# MJ808_clone_-_all_driver_-_23mm.net
KiCad netlist of a schematic drawn in EAGLE
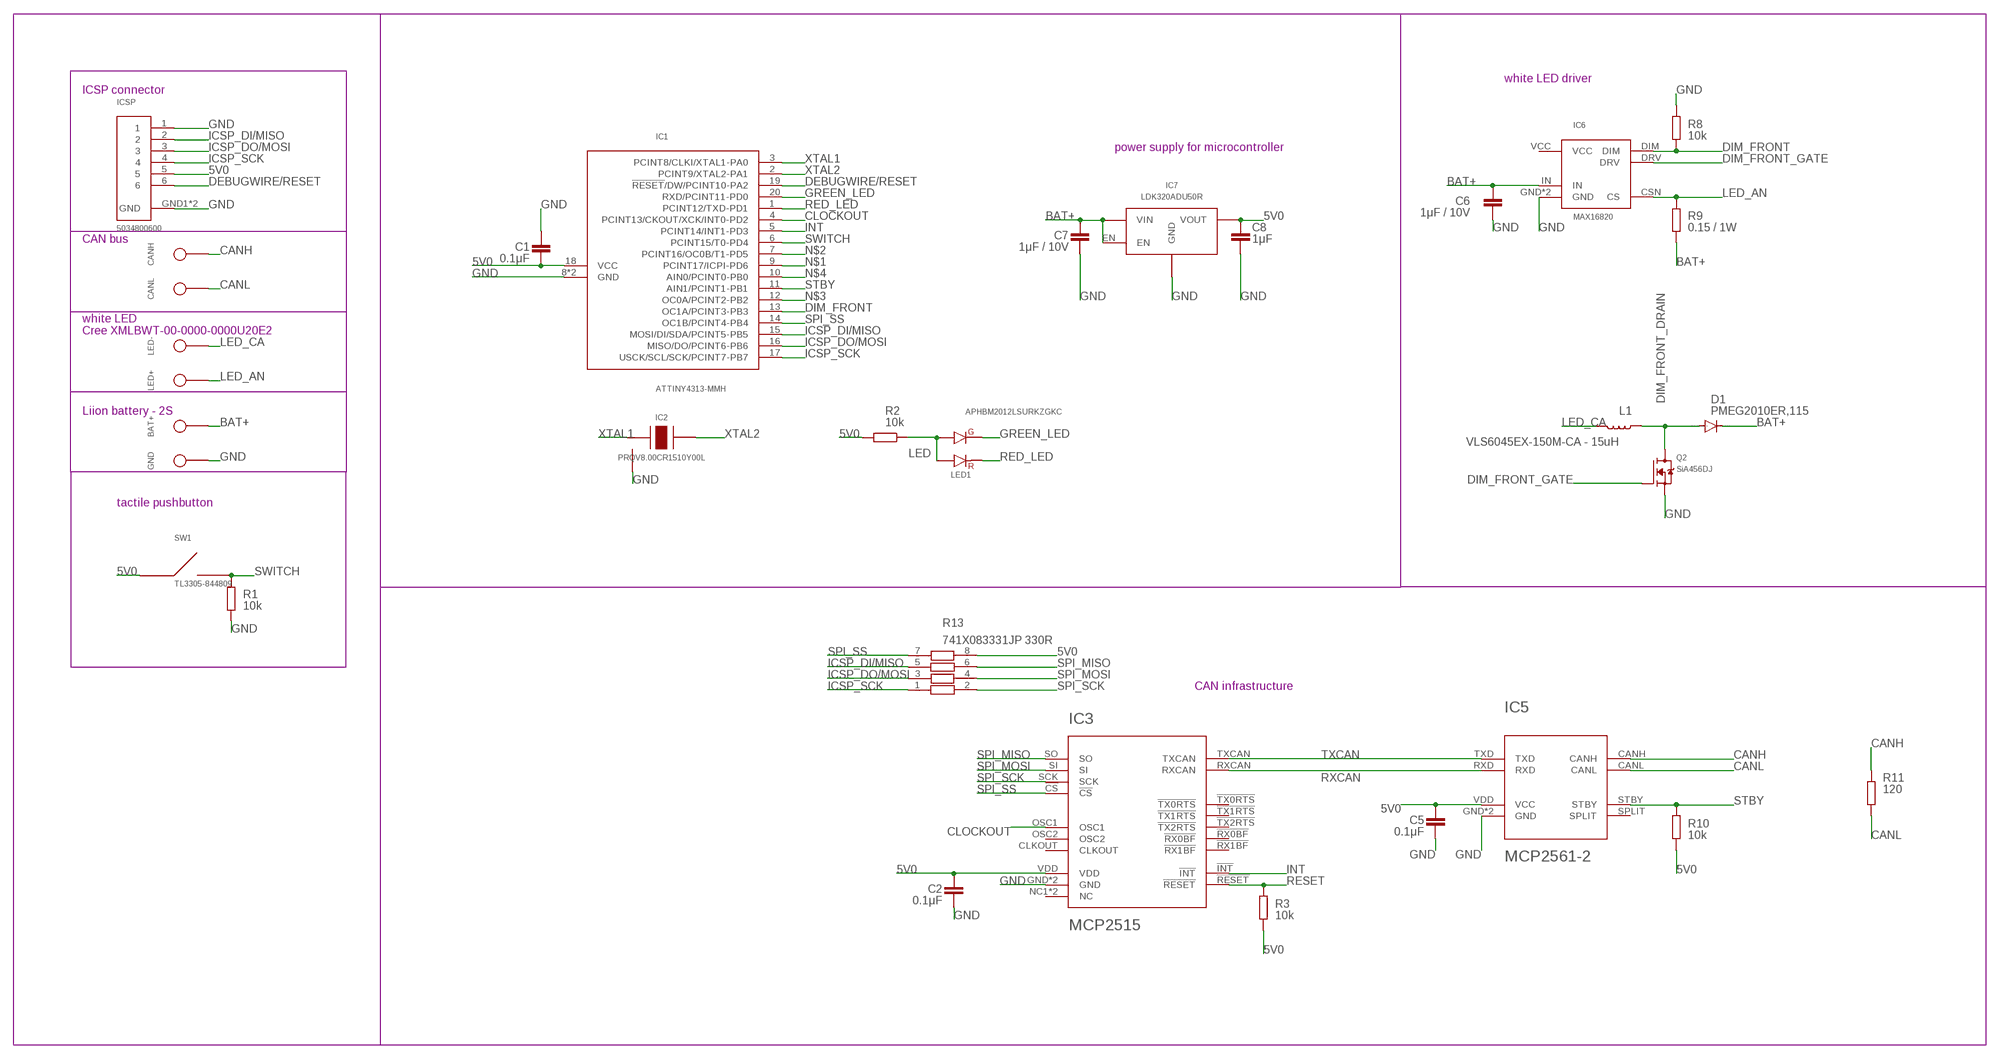
[diagram p0: schematic, sheet 1]

(export (version "E")
  (design (tool "Eeschema 10.0.6"))
  (components
    (comp (ref "BAT+")
      (value "LiIon + Terminal")
      (footprint "eagle-import:TH")
      (libsource (lib "eagle-import") (part "TP"))
    )
    (comp (ref "C1")
      (value "0.1μF")
      (footprint "eagle-import:C0402")
      (libsource (lib "eagle-import") (part "C-EUC0402"))
    )
    (comp (ref "C2")
      (value "0.1μF")
      (footprint "eagle-import:C0402")
      (libsource (lib "eagle-import") (part "C-EUC0402"))
    )
    (comp (ref "C5")
      (value "0.1μF")
      (footprint "eagle-import:C0402")
      (libsource (lib "eagle-import") (part "C-EUC0402"))
    )
    (comp (ref "C6")
      (value "1μF / 10V")
      (footprint "eagle-import:C0402")
      (libsource (lib "eagle-import") (part "C-EUC0402"))
    )
    (comp (ref "C7")
      (value "1μF / 10V")
      (footprint "eagle-import:C0402")
      (libsource (lib "eagle-import") (part "C-EUC0402"))
    )
    (comp (ref "C8")
      (value "1μF")
      (footprint "eagle-import:C0402")
      (libsource (lib "eagle-import") (part "C-EUC0402"))
    )
    (comp (ref "CANH")
      (value "CAN high")
      (footprint "eagle-import:TH")
      (libsource (lib "eagle-import") (part "TP"))
    )
    (comp (ref "CANL")
      (value "CAN low")
      (footprint "eagle-import:TH")
      (libsource (lib "eagle-import") (part "TP"))
    )
    (comp (ref "D1")
      (value "PMEG2010ER,115")
      (footprint "eagle-import:SOD123")
      (libsource (lib "eagle-import") (part "DIODE-SOD123"))
    )
    (comp (ref "GND")
      (value "LiIon - Terminal")
      (footprint "eagle-import:TH")
      (libsource (lib "eagle-import") (part "TP"))
    )
    (comp (ref "IC1")
      (value "ATTINY4313-MMH")
      (footprint "eagle-import:VQFN-20")
      (fields (field (name "SPICEPREFIX") "X"))
      (libsource (lib "eagle-import") (part "ATTINY4313VQFN-20"))
    )
    (comp (ref "IC2")
      (value "PRQV8.00CR1510Y00L")
      (footprint "eagle-import:SMT")
      (libsource (lib "eagle-import") (part "PRQV"))
    )
    (comp (ref "IC3")
      (value "MCP2515")
      (footprint "eagle-import:QFN20")
      (libsource (lib "eagle-import") (part "MCP2515-I-ML"))
    )
    (comp (ref "IC5")
      (value "MCP2561-2")
      (footprint "eagle-import:DFN10")
      (libsource (lib "eagle-import") (part "MCP2561-2"))
    )
    (comp (ref "IC6")
      (value "MAX16820")
      (footprint "eagle-import:TDFN-6-EP")
      (libsource (lib "eagle-import") (part "MAX16820"))
    )
    (comp (ref "IC7")
      (value "LDK320ADU50R")
      (footprint "eagle-import:SOT-23-5L")
      (libsource (lib "eagle-import") (part "LDK320SOT-23-5L"))
    )
    (comp (ref "ICSP")
      (value "5034800600")
      (footprint "eagle-import:SMT")
      (libsource (lib "eagle-import") (part "5034800600"))
    )
    (comp (ref "L1")
      (value "VLS6045EX-150M-CA - 15uH")
      (footprint "eagle-import:SRN6045")
      (libsource (lib "eagle-import") (part "INDUCTOR-SRN6045-33UH"))
    )
    (comp (ref "LED+")
      (value "LED anode")
      (footprint "eagle-import:TH")
      (libsource (lib "eagle-import") (part "TP"))
    )
    (comp (ref "LED-")
      (value "LED cathode")
      (footprint "eagle-import:TH")
      (libsource (lib "eagle-import") (part "TP"))
    )
    (comp (ref "LED1")
      (value "APHBM2012LSURKZGKC")
      (footprint "eagle-import:SMD")
      (libsource (lib "eagle-import") (part "APHBM2012LSURKZGKC"))
    )
    (comp (ref "Q2")
      (value "SiA456DJ")
      (footprint "eagle-import:SC-70-6")
      (libsource (lib "eagle-import") (part "SIA456DJ"))
    )
    (comp (ref "R1")
      (value "10k")
      (footprint "eagle-import:R0402")
      (libsource (lib "eagle-import") (part "R-EU_R0402"))
    )
    (comp (ref "R2")
      (value "10k")
      (footprint "eagle-import:R0402")
      (libsource (lib "eagle-import") (part "R-EU_R0402"))
    )
    (comp (ref "R3")
      (value "10k")
      (footprint "eagle-import:R0402")
      (libsource (lib "eagle-import") (part "R-EU_R0402"))
    )
    (comp (ref "R8")
      (value "10k")
      (footprint "eagle-import:R0402")
      (libsource (lib "eagle-import") (part "R-EU_R0402"))
    )
    (comp (ref "R9")
      (value "0.15 / 1W")
      (footprint "eagle-import:R1210")
      (libsource (lib "eagle-import") (part "R-EU_R1210"))
    )
    (comp (ref "R10")
      (value "10k")
      (footprint "eagle-import:R0402")
      (libsource (lib "eagle-import") (part "R-EU_R0402"))
    )
    (comp (ref "R11")
      (value "120")
      (footprint "eagle-import:R0805")
      (libsource (lib "eagle-import") (part "R-EU_R0805"))
    )
    (comp (ref "R13")
      (value "741X083331JP 330R")
      (footprint "eagle-import:0402")
      (libsource (lib "eagle-import") (part "741X083331JP"))
    )
    (comp (ref "SW1")
      (value "TL3305-844809")
      (footprint "eagle-import:SMD")
      (libsource (lib "eagle-import") (part "TL3305-844809"))
    )
  )
  (nets
    (net (code "1") (name "/5V0") (class "Default")
      (node (ref "C1") (pin "1") (pinfunction "1_1") (pintype "passive"))
      (node (ref "C2") (pin "1") (pinfunction "1_1") (pintype "passive"))
      (node (ref "C5") (pin "1") (pinfunction "1_1") (pintype "passive"))
      (node (ref "C8") (pin "2") (pinfunction "2_2") (pintype "passive"))
      (node (ref "IC1") (pin "18") (pinfunction "VCC_18") (pintype "bidirectional"))
      (node (ref "IC3") (pin "VDD") (pinfunction "VDD_VDD") (pintype "power_in"))
      (node (ref "IC5") (pin "VDD") (pinfunction "VCC_VDD") (pintype "power_in"))
      (node (ref "IC7") (pin "OUT") (pinfunction "VOUT_OUT") (pintype "bidirectional"))
      (node (ref "ICSP") (pin "5") (pinfunction "5_5") (pintype "bidirectional"))
      (node (ref "R10") (pin "1") (pinfunction "1_1") (pintype "passive"))
      (node (ref "R13") (pin "8") (pinfunction "8_8") (pintype "bidirectional"))
      (node (ref "R2") (pin "2") (pinfunction "2_2") (pintype "passive"))
      (node (ref "R3") (pin "1") (pinfunction "1_1") (pintype "passive"))
      (node (ref "SW1") (pin "1") (pinfunction "P$1_1") (pintype "bidirectional"))
      (node (ref "SW1") (pin "2") (pinfunction "P$1_2") (pintype "bidirectional"))
    )
    (net (code "2") (name "/BAT+") (class "Default")
      (node (ref "BAT+") (pin "TP$1") (pinfunction "TP$1_TP$1") (pintype "bidirectional"))
      (node (ref "C6") (pin "1") (pinfunction "1_1") (pintype "passive"))
      (node (ref "C7") (pin "1") (pinfunction "1_1") (pintype "passive"))
      (node (ref "D1") (pin "C") (pinfunction "C_C") (pintype "passive"))
      (node (ref "IC6") (pin "IN") (pinfunction "IN_IN") (pintype "power_in"))
      (node (ref "IC7") (pin "EN") (pinfunction "EN_EN") (pintype "bidirectional"))
      (node (ref "IC7") (pin "IN") (pinfunction "VIN_IN") (pintype "bidirectional"))
      (node (ref "R9") (pin "2") (pinfunction "2_2") (pintype "passive"))
    )
    (net (code "3") (name "/CANH") (class "Default")
      (node (ref "CANH") (pin "TP$1") (pinfunction "TP$1_TP$1") (pintype "bidirectional"))
      (node (ref "IC5") (pin "CANH") (pinfunction "CANH_CANH") (pintype "bidirectional"))
      (node (ref "R11") (pin "2") (pinfunction "2_2") (pintype "passive"))
    )
    (net (code "4") (name "/CANL") (class "Default")
      (node (ref "CANL") (pin "TP$1") (pinfunction "TP$1_TP$1") (pintype "bidirectional"))
      (node (ref "IC5") (pin "CANL") (pinfunction "CANL_CANL") (pintype "bidirectional"))
      (node (ref "R11") (pin "1") (pinfunction "1_1") (pintype "passive"))
    )
    (net (code "5") (name "/CLOCKOUT") (class "Default")
      (node (ref "IC1") (pin "4") (pinfunction "PCINT13/CKOUT/XCK/INT0-PD2_4") (pintype "bidirectional"))
      (node (ref "IC3") (pin "OSC1") (pinfunction "OSC1_OSC1") (pintype "bidirectional"))
    )
    (net (code "6") (name "/DEBUGWIRE{slash}RESET") (class "Default")
      (node (ref "IC1") (pin "19") (pinfunction "~{RESET}/DW/PCINT10-PA2_19") (pintype "bidirectional"))
      (node (ref "ICSP") (pin "6") (pinfunction "6_6") (pintype "bidirectional"))
    )
    (net (code "7") (name "/DIM_FRONT") (class "Default")
      (node (ref "IC1") (pin "13") (pinfunction "OC1A/PCINT3-PB3_13") (pintype "bidirectional"))
      (node (ref "IC6") (pin "DIM") (pinfunction "DIM_DIM") (pintype "bidirectional"))
      (node (ref "R8") (pin "1") (pinfunction "1_1") (pintype "passive"))
    )
    (net (code "8") (name "/DIM_FRONT_DRAIN") (class "Default")
      (node (ref "D1") (pin "A") (pinfunction "A_A") (pintype "passive"))
      (node (ref "L1") (pin "1") (pinfunction "1_1") (pintype "passive"))
      (node (ref "Q2") (pin "1D") (pinfunction "D_1D") (pintype "passive"))
      (node (ref "Q2") (pin "2D") (pinfunction "D_2D") (pintype "passive"))
      (node (ref "Q2") (pin "5D") (pinfunction "D_5D") (pintype "passive"))
      (node (ref "Q2") (pin "6D") (pinfunction "D_6D") (pintype "passive"))
      (node (ref "Q2") (pin "D") (pinfunction "D_D") (pintype "passive"))
    )
    (net (code "9") (name "/DIM_FRONT_GATE") (class "Default")
      (node (ref "IC6") (pin "DRV") (pinfunction "DRV_DRV") (pintype "bidirectional"))
      (node (ref "Q2") (pin "3G") (pinfunction "G_3G") (pintype "passive"))
    )
    (net (code "10") (name "/GND") (class "Default")
      (node (ref "C1") (pin "2") (pinfunction "2_2") (pintype "passive"))
      (node (ref "C2") (pin "2") (pinfunction "2_2") (pintype "passive"))
      (node (ref "C5") (pin "2") (pinfunction "2_2") (pintype "passive"))
      (node (ref "C6") (pin "2") (pinfunction "2_2") (pintype "passive"))
      (node (ref "C7") (pin "2") (pinfunction "2_2") (pintype "passive"))
      (node (ref "C8") (pin "1") (pinfunction "1_1") (pintype "passive"))
      (node (ref "GND") (pin "TP$1") (pinfunction "TP$1_TP$1") (pintype "bidirectional"))
      (node (ref "IC1") (pin "8") (pinfunction "GND_8") (pintype "bidirectional"))
      (node (ref "IC1") (pin "GND") (pinfunction "GND_GND") (pintype "bidirectional"))
      (node (ref "IC2") (pin "GND") (pinfunction "GND_GND") (pintype "bidirectional"))
      (node (ref "IC3") (pin "GND") (pinfunction "GND_GND") (pintype "power_in"))
      (node (ref "IC3") (pin "GND6") (pinfunction "GND_GND6") (pintype "power_in"))
      (node (ref "IC5") (pin "GND") (pinfunction "GND_GND") (pintype "power_in"))
      (node (ref "IC5") (pin "VSS") (pinfunction "GND_VSS") (pintype "power_in"))
      (node (ref "IC6") (pin "GND") (pinfunction "GND_GND") (pintype "power_in"))
      (node (ref "IC6") (pin "GND1") (pinfunction "GND_GND1") (pintype "power_in"))
      (node (ref "IC7") (pin "GND") (pinfunction "GND_GND") (pintype "bidirectional"))
      (node (ref "ICSP") (pin "1") (pinfunction "1_1") (pintype "bidirectional"))
      (node (ref "ICSP") (pin "GND1") (pinfunction "GND_GND1") (pintype "bidirectional"))
      (node (ref "ICSP") (pin "GND2") (pinfunction "GND_GND2") (pintype "bidirectional"))
      (node (ref "Q2") (pin "4S") (pinfunction "S_4S") (pintype "passive"))
      (node (ref "Q2") (pin "S") (pinfunction "S_S") (pintype "passive"))
      (node (ref "R1") (pin "2") (pinfunction "2_2") (pintype "passive"))
      (node (ref "R8") (pin "2") (pinfunction "2_2") (pintype "passive"))
    )
    (net (code "11") (name "/GREEN_LED") (class "Default")
      (node (ref "IC1") (pin "20") (pinfunction "RXD/PCINT11-PD0_20") (pintype "bidirectional"))
      (node (ref "LED1") (pin "3") (pinfunction "3_3") (pintype "bidirectional"))
    )
    (net (code "12") (name "/ICSP_DI{slash}MISO") (class "Default")
      (node (ref "IC1") (pin "15") (pinfunction "MOSI/DI/SDA/PCINT5-PB5_15") (pintype "bidirectional"))
      (node (ref "ICSP") (pin "2") (pinfunction "2_2") (pintype "bidirectional"))
      (node (ref "R13") (pin "5") (pinfunction "5_5") (pintype "bidirectional"))
    )
    (net (code "13") (name "/ICSP_DO{slash}MOSI") (class "Default")
      (node (ref "IC1") (pin "16") (pinfunction "MISO/DO/PCINT6-PB6_16") (pintype "bidirectional"))
      (node (ref "ICSP") (pin "3") (pinfunction "3_3") (pintype "bidirectional"))
      (node (ref "R13") (pin "3") (pinfunction "3_3") (pintype "bidirectional"))
    )
    (net (code "14") (name "/ICSP_SCK") (class "Default")
      (node (ref "IC1") (pin "17") (pinfunction "USCK/SCL/SCK/PCINT7-PB7_17") (pintype "bidirectional"))
      (node (ref "ICSP") (pin "4") (pinfunction "4_4") (pintype "bidirectional"))
      (node (ref "R13") (pin "1") (pinfunction "1_1") (pintype "bidirectional"))
    )
    (net (code "15") (name "/INT") (class "Default")
      (node (ref "IC1") (pin "5") (pinfunction "PCINT14/INT1-PD3_5") (pintype "bidirectional"))
      (node (ref "IC3") (pin "!INT!") (pinfunction "~{INT}_!INT!") (pintype "bidirectional"))
    )
    (net (code "16") (name "/LED") (class "Default")
      (node (ref "LED1") (pin "1") (pinfunction "1_1") (pintype "bidirectional"))
      (node (ref "LED1") (pin "4") (pinfunction "4_4") (pintype "bidirectional"))
      (node (ref "R2") (pin "1") (pinfunction "1_1") (pintype "passive"))
    )
    (net (code "17") (name "/LED_AN") (class "Default")
      (node (ref "IC6") (pin "CSN") (pinfunction "CS_CSN") (pintype "bidirectional"))
      (node (ref "LED+") (pin "TP$1") (pinfunction "TP$1_TP$1") (pintype "bidirectional"))
      (node (ref "R9") (pin "1") (pinfunction "1_1") (pintype "passive"))
    )
    (net (code "18") (name "/LED_CA") (class "Default")
      (node (ref "L1") (pin "2") (pinfunction "2_2") (pintype "passive"))
      (node (ref "LED-") (pin "TP$1") (pinfunction "TP$1_TP$1") (pintype "bidirectional"))
    )
    (net (code "19") (name "/N$1") (class "Default")
      (node (ref "IC1") (pin "9") (pinfunction "PCINT17/ICPI-PD6_9") (pintype "bidirectional"))
    )
    (net (code "20") (name "/N$2") (class "Default")
      (node (ref "IC1") (pin "7") (pinfunction "PCINT16/OC0B/T1-PD5_7") (pintype "bidirectional"))
    )
    (net (code "21") (name "/N$3") (class "Default")
      (node (ref "IC1") (pin "12") (pinfunction "OC0A/PCINT2-PB2_12") (pintype "bidirectional"))
    )
    (net (code "22") (name "/N$4") (class "Default")
      (node (ref "IC1") (pin "10") (pinfunction "AIN0/PCINT0-PB0_10") (pintype "bidirectional"))
    )
    (net (code "23") (name "/RED_LED") (class "Default")
      (node (ref "IC1") (pin "1") (pinfunction "PCINT12/TXD-PD1_1") (pintype "bidirectional"))
      (node (ref "LED1") (pin "2") (pinfunction "2_2") (pintype "bidirectional"))
    )
    (net (code "24") (name "/RESET") (class "Default")
      (node (ref "IC3") (pin "!RESET!") (pinfunction "~{RESET}_!RESET!") (pintype "bidirectional"))
      (node (ref "R3") (pin "2") (pinfunction "2_2") (pintype "passive"))
    )
    (net (code "25") (name "/RXCAN") (class "Default")
      (node (ref "IC3") (pin "RXCAN") (pinfunction "RXCAN_RXCAN") (pintype "input"))
      (node (ref "IC5") (pin "RXD") (pinfunction "RXD_RXD") (pintype "output"))
    )
    (net (code "26") (name "/SPI_MISO") (class "Default")
      (node (ref "IC3") (pin "SO") (pinfunction "SO_SO") (pintype "output"))
      (node (ref "R13") (pin "6") (pinfunction "6_6") (pintype "bidirectional"))
    )
    (net (code "27") (name "/SPI_MOSI") (class "Default")
      (node (ref "IC3") (pin "SI") (pinfunction "SI_SI") (pintype "input"))
      (node (ref "R13") (pin "4") (pinfunction "4_4") (pintype "bidirectional"))
    )
    (net (code "28") (name "/SPI_SCK") (class "Default")
      (node (ref "IC3") (pin "SCK") (pinfunction "SCK_SCK") (pintype "bidirectional"))
      (node (ref "R13") (pin "2") (pinfunction "2_2") (pintype "bidirectional"))
    )
    (net (code "29") (name "/SPI_SS") (class "Default")
      (node (ref "IC1") (pin "14") (pinfunction "OC1B/PCINT4-PB4_14") (pintype "bidirectional"))
      (node (ref "IC3") (pin "!CS!") (pinfunction "~{CS}_!CS!") (pintype "bidirectional"))
      (node (ref "R13") (pin "7") (pinfunction "7_7") (pintype "bidirectional"))
    )
    (net (code "30") (name "/STBY") (class "Default")
      (node (ref "IC1") (pin "11") (pinfunction "AIN1/PCINT1-PB1_11") (pintype "bidirectional"))
      (node (ref "IC5") (pin "STBY") (pinfunction "STBY_STBY") (pintype "bidirectional"))
      (node (ref "R10") (pin "2") (pinfunction "2_2") (pintype "passive"))
    )
    (net (code "31") (name "/SWITCH") (class "Default")
      (node (ref "IC1") (pin "6") (pinfunction "PCINT15/T0-PD4_6") (pintype "bidirectional"))
      (node (ref "R1") (pin "1") (pinfunction "1_1") (pintype "passive"))
      (node (ref "SW1") (pin "3") (pinfunction "P$2_3") (pintype "bidirectional"))
      (node (ref "SW1") (pin "4") (pinfunction "P$2_4") (pintype "bidirectional"))
    )
    (net (code "32") (name "/TXCAN") (class "Default")
      (node (ref "IC3") (pin "TXCAN") (pinfunction "TXCAN_TXCAN") (pintype "output"))
      (node (ref "IC5") (pin "TXD") (pinfunction "TXD_TXD") (pintype "input"))
    )
    (net (code "33") (name "/VCC") (class "Default")
      (node (ref "IC6") (pin "VCC") (pinfunction "VCC_VCC") (pintype "power_in"))
    )
    (net (code "34") (name "/XTAL1") (class "Default")
      (node (ref "IC1") (pin "3") (pinfunction "PCINT8/CLKI/XTAL1-PA0_3") (pintype "bidirectional"))
      (node (ref "IC2") (pin "XTAL1") (pinfunction "XTAL1_XTAL1") (pintype "bidirectional"))
    )
    (net (code "35") (name "/XTAL2") (class "Default")
      (node (ref "IC1") (pin "2") (pinfunction "PCINT9/XTAL2-PA1_2") (pintype "bidirectional"))
      (node (ref "IC2") (pin "XTAL2") (pinfunction "XTAL2_XTAL2") (pintype "bidirectional"))
    )
    (net (code "36") (name "unconnected-(IC3-NC-PadNC1)") (class "Default")
      (node (ref "IC3") (pin "NC1") (pinfunction "NC_NC1") (pintype "no_connect"))
    )
    (net (code "37") (name "unconnected-(IC3-NC-PadNC2)") (class "Default")
      (node (ref "IC3") (pin "NC2") (pinfunction "NC_NC2") (pintype "no_connect"))
    )
    (net (code "38") (name "unconnected-(IC3-PadCLKOUT)") (class "Default")
      (node (ref "IC3") (pin "CLKOUT") (pinfunction "CLKOUT_CLKOUT") (pintype "bidirectional"))
    )
    (net (code "39") (name "unconnected-(IC3-PadOSC2)") (class "Default")
      (node (ref "IC3") (pin "OSC2") (pinfunction "OSC2_OSC2") (pintype "bidirectional"))
    )
    (net (code "40") (name "unconnected-(IC3-~{RX0BF}-Pad!RX0BF!)") (class "Default")
      (node (ref "IC3") (pin "!RX0BF!") (pinfunction "~{RX0BF}_!RX0BF!") (pintype "bidirectional"))
    )
    (net (code "41") (name "unconnected-(IC3-~{RX1BF}-Pad!RX1BF!)") (class "Default")
      (node (ref "IC3") (pin "!RX1BF!") (pinfunction "~{RX1BF}_!RX1BF!") (pintype "bidirectional"))
    )
    (net (code "42") (name "unconnected-(IC3-~{TX0RTS}-Pad!TX0RTS!)") (class "Default")
      (node (ref "IC3") (pin "!TX0RTS!") (pinfunction "~{TX0RTS}_!TX0RTS!") (pintype "bidirectional"))
    )
    (net (code "43") (name "unconnected-(IC3-~{TX1RTS}-Pad!TX1RTS!)") (class "Default")
      (node (ref "IC3") (pin "!TX1RTS!") (pinfunction "~{TX1RTS}_!TX1RTS!") (pintype "bidirectional"))
    )
    (net (code "44") (name "unconnected-(IC3-~{TX2RTS}-Pad!TX2RTS!)") (class "Default")
      (node (ref "IC3") (pin "!TX2RTS!") (pinfunction "~{TX2RTS}_!TX2RTS!") (pintype "bidirectional"))
    )
    (net (code "45") (name "unconnected-(IC5-PadSPLIT)") (class "Default")
      (node (ref "IC5") (pin "SPLIT") (pinfunction "SPLIT_SPLIT") (pintype "bidirectional"))
    )
  )
)
